# Nutriente_inferior.net
KiCad netlist of a schematic drawn in EAGLE
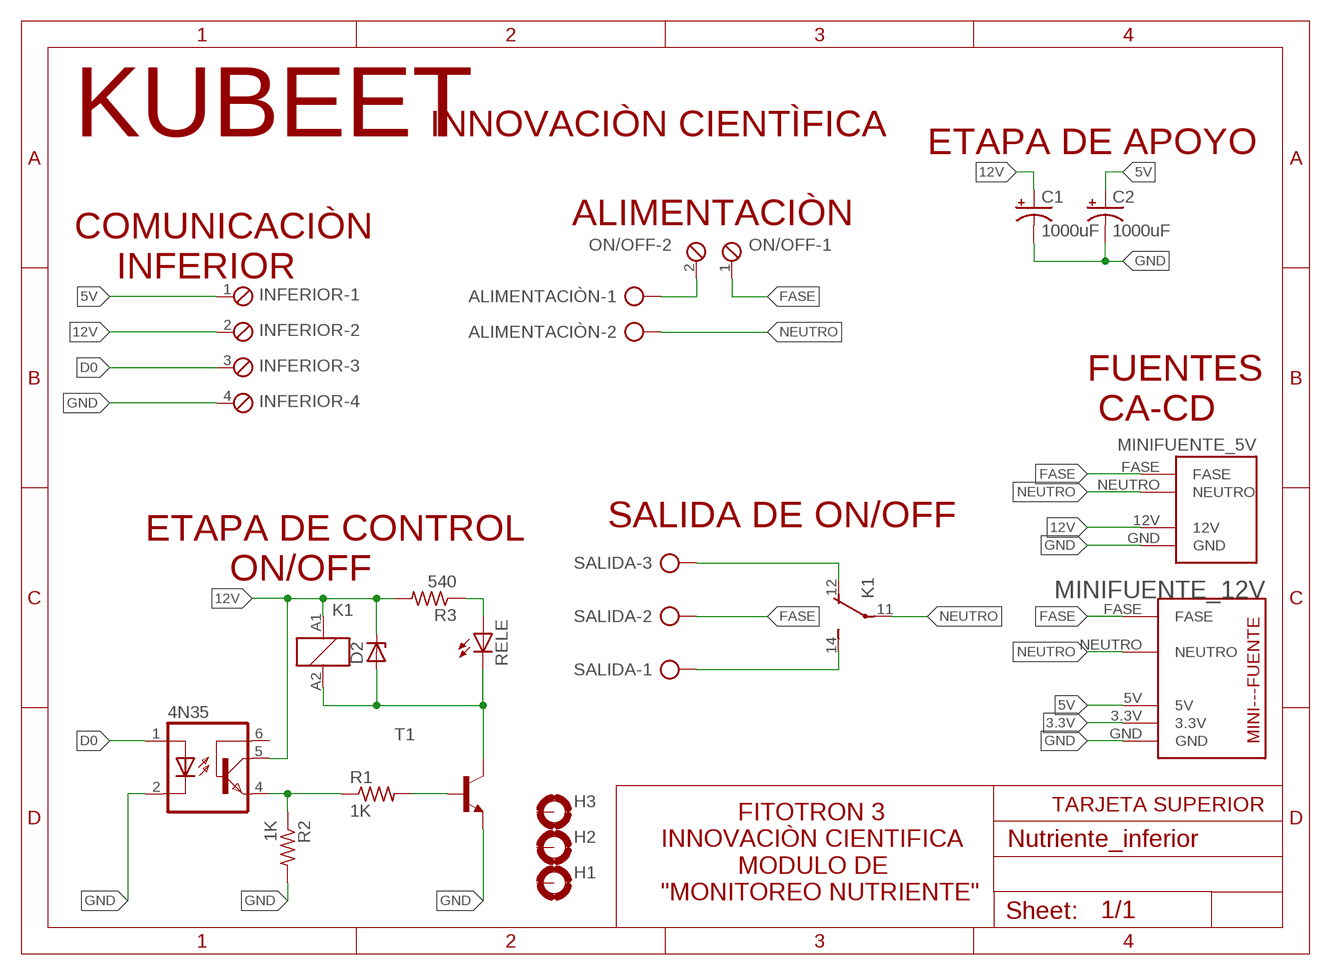
[diagram p0: schematic, sheet 1]

(export (version "E")
  (design (tool "Eeschema 10.0.6"))
  (components
    (comp (ref "4N35")
      (value "4N35")
      (footprint "eagle-import:DIL06")
      (fields (field (name "MF") "FAIRCHILD SEMICONDUCTOR"))
      (libsource (lib "eagle-import") (part "4N35"))
    )
    (comp (ref "ALIMENTACIÒN")
      (value "AK300/2")
      (footprint "eagle-import:AK300_2")
      (libsource (lib "eagle-import") (part "AK300/2"))
    )
    (comp (ref "C1")
      (value "1000uF")
      (footprint "eagle-import:E3,5-10")
      (libsource (lib "eagle-import") (part "CPOL-USE3.5-10"))
    )
    (comp (ref "C2")
      (value "1000uF")
      (footprint "eagle-import:E3,5-10")
      (libsource (lib "eagle-import") (part "CPOL-USE3.5-10"))
    )
    (comp (ref "D2")
      (value "1N821")
      (footprint "eagle-import:DO35Z10")
      (libsource (lib "eagle-import") (part "1N821"))
    )
    (comp (ref "H1")
      (value "MOUNT-PAD-ROUND3.0")
      (footprint "eagle-import:3,0-PAD")
      (libsource (lib "eagle-import") (part "MOUNT-PAD-ROUND3.0"))
    )
    (comp (ref "H2")
      (value "MOUNT-PAD-ROUND3.0")
      (footprint "eagle-import:3,0-PAD")
      (libsource (lib "eagle-import") (part "MOUNT-PAD-ROUND3.0"))
    )
    (comp (ref "H3")
      (value "MOUNT-PAD-ROUND3.0")
      (footprint "eagle-import:3,0-PAD")
      (libsource (lib "eagle-import") (part "MOUNT-PAD-ROUND3.0"))
    )
    (comp (ref "INFERIOR")
      (value "MPT4")
      (footprint "eagle-import:4POL254")
      (libsource (lib "eagle-import") (part "MPT4"))
    )
    (comp (ref "K1")
      (value "ZNS5112")
      (footprint "eagle-import:ZN5")
      (libsource (lib "eagle-import") (part "ZNS5112"))
    )
    (comp (ref "MINIFUENTE_5V")
      (value "MINIFUENTE4")
      (footprint "eagle-import:MINIFUENTE4")
      (libsource (lib "eagle-import") (part "MINIFUENTE4"))
    )
    (comp (ref "MINIFUENTE_12V")
      (value "MINIFUENTE3")
      (footprint "eagle-import:MINIFUENTE3")
      (libsource (lib "eagle-import") (part "MINIFUENTE3"))
    )
    (comp (ref "ON/OFF")
      (value "MPT2")
      (footprint "eagle-import:2POL254")
      (libsource (lib "eagle-import") (part "MPT2"))
    )
    (comp (ref "R1")
      (value "1K")
      (footprint "eagle-import:0207_7")
      (libsource (lib "eagle-import") (part "R-US_0207/7"))
    )
    (comp (ref "R2")
      (value "1K")
      (footprint "eagle-import:0207_7")
      (libsource (lib "eagle-import") (part "R-US_0207/7"))
    )
    (comp (ref "R3")
      (value "540")
      (footprint "eagle-import:0207_7")
      (libsource (lib "eagle-import") (part "R-US_0207/7"))
    )
    (comp (ref "RELE")
      (value "LED5MM")
      (footprint "eagle-import:LED5MM")
      (libsource (lib "eagle-import") (part "LED5MM"))
    )
    (comp (ref "SALIDA")
      (value "AK300/3")
      (footprint "eagle-import:AK300_3")
      (libsource (lib "eagle-import") (part "AK300/3"))
    )
    (comp (ref "T1")
      (value "2N2222-NPN-TO92-EBC")
      (footprint "eagle-import:TO92-EBC")
      (libsource (lib "eagle-import") (part "-NPN-TO92-EBC2N2222"))
    )
  )
  (nets
    (net (code "1") (name "3.3V") (class "Default")
      (node (ref "MINIFUENTE_12V") (pin "3.3V") (pinfunction "3.3V_3.3V") (pintype "bidirectional"))
    )
    (net (code "2") (name "5V") (class "Default")
      (node (ref "C2") (pin "+") (pinfunction "+_+") (pintype "passive"))
      (node (ref "INFERIOR") (pin "1") (pinfunction "1_1") (pintype "passive"))
      (node (ref "MINIFUENTE_12V") (pin "5V") (pinfunction "5V_5V") (pintype "bidirectional"))
    )
    (net (code "3") (name "12V") (class "Default")
      (node (ref "4N35") (pin "5") (pinfunction "COL_5") (pintype "passive"))
      (node (ref "C1") (pin "+") (pinfunction "+_+") (pintype "passive"))
      (node (ref "D2") (pin "C") (pinfunction "C_C") (pintype "passive"))
      (node (ref "INFERIOR") (pin "2") (pinfunction "1_2") (pintype "passive"))
      (node (ref "K1") (pin "A1") (pinfunction "1_A1") (pintype "passive"))
      (node (ref "MINIFUENTE_5V") (pin "12V") (pinfunction "12V_12V") (pintype "bidirectional"))
      (node (ref "R3") (pin "2") (pinfunction "2_2") (pintype "passive"))
    )
    (net (code "4") (name "D0") (class "Default")
      (node (ref "4N35") (pin "1") (pinfunction "A_1") (pintype "passive"))
      (node (ref "INFERIOR") (pin "3") (pinfunction "1_3") (pintype "passive"))
    )
    (net (code "5") (name "FASE") (class "Default")
      (node (ref "MINIFUENTE_12V") (pin "FASE") (pinfunction "FASE_FASE") (pintype "bidirectional"))
      (node (ref "MINIFUENTE_5V") (pin "FASE") (pinfunction "FASE_FASE") (pintype "bidirectional"))
      (node (ref "ON/OFF") (pin "1") (pinfunction "1_1") (pintype "passive"))
      (node (ref "SALIDA") (pin "2") (pinfunction "KL_2") (pintype "passive"))
    )
    (net (code "6") (name "GND") (class "Default")
      (node (ref "4N35") (pin "2") (pinfunction "C_2") (pintype "passive"))
      (node (ref "C1") (pin "-") (pinfunction "-_-") (pintype "passive"))
      (node (ref "C2") (pin "-") (pinfunction "-_-") (pintype "passive"))
      (node (ref "INFERIOR") (pin "4") (pinfunction "1_4") (pintype "passive"))
      (node (ref "MINIFUENTE_12V") (pin "GND") (pinfunction "GND_GND") (pintype "bidirectional"))
      (node (ref "MINIFUENTE_5V") (pin "GND") (pinfunction "GND_GND") (pintype "bidirectional"))
      (node (ref "R2") (pin "2") (pinfunction "2_2") (pintype "passive"))
      (node (ref "T1") (pin "E") (pinfunction "E_E") (pintype "passive"))
    )
    (net (code "7") (name "NEUTRO") (class "Default")
      (node (ref "ALIMENTACIÒN") (pin "2") (pinfunction "KL_2") (pintype "passive"))
      (node (ref "K1") (pin "11") (pinfunction "P_11") (pintype "passive"))
      (node (ref "MINIFUENTE_12V") (pin "NEUTRO") (pinfunction "NEUTRO_NEUTRO") (pintype "bidirectional"))
      (node (ref "MINIFUENTE_5V") (pin "NEUTRO") (pinfunction "NEUTRO_NEUTRO") (pintype "bidirectional"))
    )
    (net (code "8") (name "Net-(4N35-EMI)") (class "Default")
      (node (ref "4N35") (pin "4") (pinfunction "EMI_4") (pintype "passive"))
      (node (ref "R1") (pin "1") (pinfunction "1_1") (pintype "passive"))
      (node (ref "R2") (pin "1") (pinfunction "1_1") (pintype "passive"))
    )
    (net (code "9") (name "Net-(ALIMENTACIÒNA-KL)") (class "Default")
      (node (ref "ALIMENTACIÒN") (pin "1") (pinfunction "KL_1") (pintype "passive"))
      (node (ref "ON/OFF") (pin "2") (pinfunction "1_2") (pintype "passive"))
    )
    (net (code "10") (name "Net-(K1A-2)") (class "Default")
      (node (ref "D2") (pin "A") (pinfunction "A_A") (pintype "passive"))
      (node (ref "K1") (pin "A2") (pinfunction "2_A2") (pintype "passive"))
      (node (ref "RELE") (pin "K") (pinfunction "C_K") (pintype "passive"))
      (node (ref "T1") (pin "C") (pinfunction "C_C") (pintype "passive"))
    )
    (net (code "11") (name "Net-(K1B-O)") (class "Default")
      (node (ref "K1") (pin "12") (pinfunction "O_12") (pintype "passive"))
      (node (ref "SALIDA") (pin "3") (pinfunction "KL_3") (pintype "passive"))
    )
    (net (code "12") (name "Net-(K1B-S)") (class "Default")
      (node (ref "K1") (pin "14") (pinfunction "S_14") (pintype "passive"))
      (node (ref "SALIDA") (pin "1") (pinfunction "KL_1") (pintype "passive"))
    )
    (net (code "13") (name "Net-(R1-Pad2)") (class "Default")
      (node (ref "R1") (pin "2") (pinfunction "2_2") (pintype "passive"))
      (node (ref "T1") (pin "B") (pinfunction "B_B") (pintype "passive"))
    )
    (net (code "14") (name "Net-(R3-Pad1)") (class "Default")
      (node (ref "R3") (pin "1") (pinfunction "1_1") (pintype "passive"))
      (node (ref "RELE") (pin "A") (pinfunction "A_A") (pintype "passive"))
    )
    (net (code "15") (name "unconnected-(4N35-BAS-Pad6)") (class "Default")
      (node (ref "4N35") (pin "6") (pinfunction "BAS_6") (pintype "passive"))
    )
    (net (code "16") (name "unconnected-(H1-MOUNT-PadB3,0)") (class "Default")
      (node (ref "H1") (pin "B3,0") (pinfunction "MOUNT_B3,0") (pintype "passive"))
    )
    (net (code "17") (name "unconnected-(H2-MOUNT-PadB3,0)") (class "Default")
      (node (ref "H2") (pin "B3,0") (pinfunction "MOUNT_B3,0") (pintype "passive"))
    )
    (net (code "18") (name "unconnected-(H3-MOUNT-PadB3,0)") (class "Default")
      (node (ref "H3") (pin "B3,0") (pinfunction "MOUNT_B3,0") (pintype "passive"))
    )
  )
)
